# V1_0.net
KiCad netlist of a schematic drawn in Altium Designer
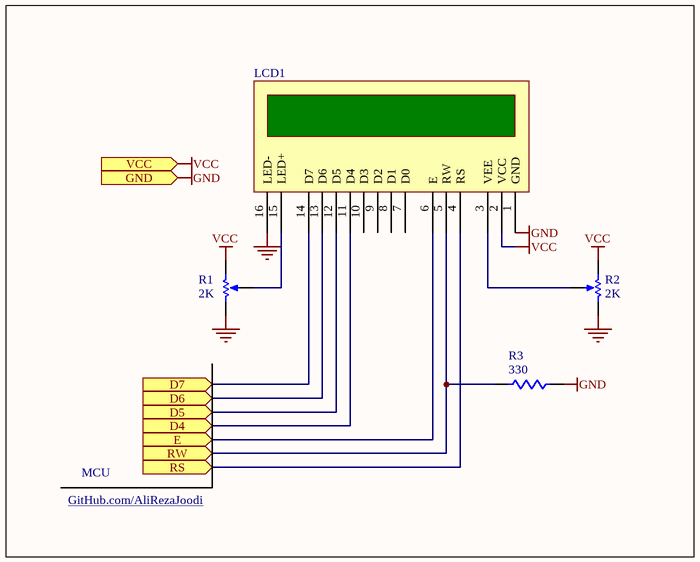
[diagram p0: V1.0.SchDoc]

(export (version "E")
  (design (tool "Eeschema 10.0.6"))
  (components
    (comp (ref "LCD1")
      (value "LCD_16*2")
      (footprint "LCD_2x16")
      (libsource (lib "Miscellaneous Devices") (part "LCD_16*2"))
    )
    (comp (ref "R1")
      (value "2K")
      (footprint "VR8-5/5.6MM")
      (description "Potentiometer")
      (fields
        (field (name "MANUFACTURER") "Generic Components")
        (field (name "Comment") "RPot1")
        (field (name "PUBLISHER") "Altium Limited")
      )
      (libsource (lib "Miscellaneous Devices") (part "RPot1"))
    )
    (comp (ref "R2")
      (value "2K")
      (footprint "VR5")
      (description "Potentiometer")
      (fields
        (field (name "MANUFACTURER") "Generic Components")
        (field (name "Comment") "RPot1")
        (field (name "PUBLISHER") "Altium Limited")
      )
      (libsource (lib "Miscellaneous Devices") (part "RPot1"))
    )
    (comp (ref "R3")
      (value "330")
      (footprint "AXIAL-0.4")
      (description "Resistor")
      (fields
        (field (name "MANUFACTURER") "Generic Components")
        (field (name "Comment") "Res1")
        (field (name "PUBLISHER") "Altium Limited")
      )
      (libsource (lib "Miscellaneous Devices") (part "Res1"))
    )
  )
  (nets
    (net (code "1") (name "/D4") (class "Default")
      (node (ref "LCD1") (pin "11") (pinfunction "D4_11") (pintype "passive"))
    )
    (net (code "2") (name "/D5") (class "Default")
      (node (ref "LCD1") (pin "12") (pinfunction "D5_12") (pintype "passive"))
    )
    (net (code "3") (name "/D6") (class "Default")
      (node (ref "LCD1") (pin "13") (pinfunction "D6_13") (pintype "passive"))
    )
    (net (code "4") (name "/D7") (class "Default")
      (node (ref "LCD1") (pin "14") (pinfunction "D7_14") (pintype "passive"))
    )
    (net (code "5") (name "/E") (class "Default")
      (node (ref "LCD1") (pin "6") (pinfunction "E_6") (pintype "passive"))
    )
    (net (code "6") (name "/RS") (class "Default")
      (node (ref "LCD1") (pin "4") (pinfunction "RS_4") (pintype "passive"))
    )
    (net (code "7") (name "/RW") (class "Default")
      (node (ref "LCD1") (pin "5") (pinfunction "RW_5") (pintype "passive"))
      (node (ref "R3") (pin "2") (pinfunction "2_2") (pintype "passive"))
    )
    (net (code "8") (name "GND") (class "Default")
      (node (ref "LCD1") (pin "1") (pinfunction "GND_1") (pintype "passive"))
      (node (ref "LCD1") (pin "16") (pinfunction "LED-_16") (pintype "passive"))
      (node (ref "R1") (pin "2") (pinfunction "BOT_2") (pintype "passive"))
      (node (ref "R2") (pin "1") (pinfunction "TOP_1") (pintype "passive"))
      (node (ref "R3") (pin "1") (pinfunction "1_1") (pintype "passive"))
    )
    (net (code "9") (name "Net-(LCD1-LED+)") (class "Default")
      (node (ref "LCD1") (pin "15") (pinfunction "LED+_15") (pintype "passive"))
      (node (ref "R1") (pin "3") (pinfunction "TAP_3") (pintype "passive"))
    )
    (net (code "10") (name "Net-(LCD1-VEE)") (class "Default")
      (node (ref "LCD1") (pin "3") (pinfunction "VEE_3") (pintype "passive"))
      (node (ref "R2") (pin "3") (pinfunction "TAP_3") (pintype "passive"))
    )
    (net (code "11") (name "VCC") (class "Default")
      (node (ref "LCD1") (pin "2") (pinfunction "VCC_2") (pintype "passive"))
      (node (ref "R1") (pin "1") (pinfunction "TOP_1") (pintype "passive"))
      (node (ref "R2") (pin "2") (pinfunction "BOT_2") (pintype "passive"))
    )
    (net (code "12") (name "unconnected-(LCD1-D0-Pad7)") (class "Default")
      (node (ref "LCD1") (pin "7") (pinfunction "D0_7") (pintype "passive"))
    )
    (net (code "13") (name "unconnected-(LCD1-D1-Pad8)") (class "Default")
      (node (ref "LCD1") (pin "8") (pinfunction "D1_8") (pintype "passive"))
    )
    (net (code "14") (name "unconnected-(LCD1-D2-Pad9)") (class "Default")
      (node (ref "LCD1") (pin "9") (pinfunction "D2_9") (pintype "passive"))
    )
    (net (code "15") (name "unconnected-(LCD1-D3-Pad10)") (class "Default")
      (node (ref "LCD1") (pin "10") (pinfunction "D3_10") (pintype "passive"))
    )
  )
)
